# 243-436_USB-to-UART.net
KiCad netlist of a schematic drawn in Altium Designer
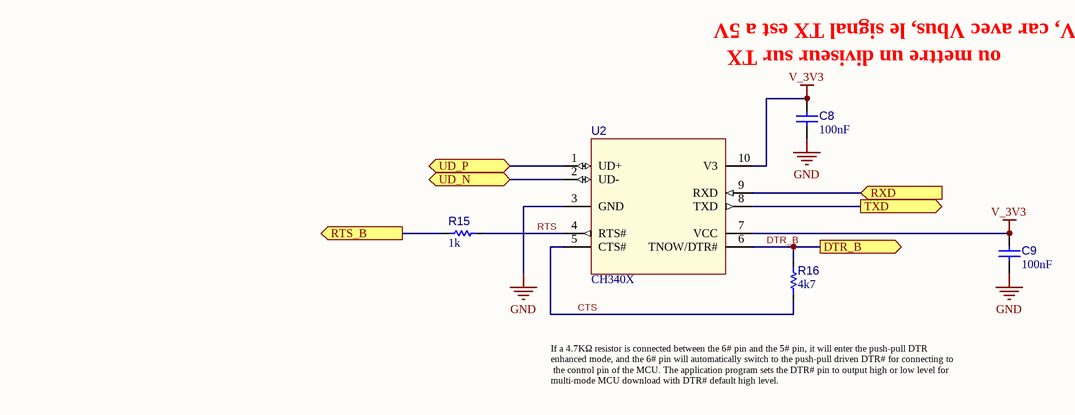
[diagram p0: 243-436_USB-to-UART.SchDoc]

(export (version "E")
  (design (tool "Eeschema 10.0.6"))
  (components
    (comp (ref "C8")
      (value "100nF")
      (footprint "C_1005[0402]")
      (description "Capacitor type 1")
      (fields (field (name "TOLERANCE") "10%") (field (name "Comment") "CAP CER 100nF 50V 0402"))
      (libsource (lib "TEP_243-Altium_DBLib") (part "capacitor"))
    )
    (comp (ref "C9")
      (value "100nF")
      (footprint "C_1005[0402]")
      (description "Capacitor type 1")
      (fields (field (name "TOLERANCE") "10%") (field (name "Comment") "CAP CER 100nF 50V 0402"))
      (libsource (lib "TEP_243-Altium_DBLib") (part "capacitor"))
    )
    (comp (ref "R15")
      (value "1k")
      (footprint "R_1005[0402]")
      (description "Resistor type 1")
      (fields (field (name "TOLERANCE") "1%") (field (name "Comment") "Res 1k 1% 0402"))
      (libsource (lib "TEP_243-Altium_DBLib") (part "resistor"))
    )
    (comp (ref "R16")
      (value "4k7")
      (footprint "R_1005[0402]")
      (description "Resistor type 1")
      (fields (field (name "TOLERANCE") "1%") (field (name "Comment") "Res 4k7 1% 0402"))
      (libsource (lib "TEP_243-Altium_DBLib") (part "resistor"))
    )
    (comp (ref "U2")
      (value "CH340X")
      (footprint "U_MSOP50P300X500-10(RM-10)_WO-TP")
      (description "IC USB to Serial Port")
      (libsource (lib "243-336_MP_Manette") (part "U_CH340X"))
    )
  )
  (nets
    (net (code "1") (name "/CTS") (class "Default")
      (node (ref "R16") (pin "1") (pinfunction "1_1") (pintype "passive"))
      (node (ref "U2") (pin "5") (pinfunction "CTS#_5") (pintype "passive"))
    )
    (net (code "2") (name "/DTR_B") (class "Default")
      (node (ref "R16") (pin "2") (pinfunction "2_2") (pintype "passive"))
      (node (ref "U2") (pin "6") (pinfunction "TNOW/DTR#_6") (pintype "passive"))
    )
    (net (code "3") (name "/RTS") (class "Default")
      (node (ref "R15") (pin "2") (pinfunction "2_2") (pintype "passive"))
      (node (ref "U2") (pin "4") (pinfunction "RTS#_4") (pintype "output"))
    )
    (net (code "4") (name "/RTS_B") (class "Default")
      (node (ref "R15") (pin "1") (pinfunction "1_1") (pintype "passive"))
    )
    (net (code "5") (name "/RXD") (class "Default")
      (node (ref "U2") (pin "9") (pinfunction "RXD_9") (pintype "input"))
    )
    (net (code "6") (name "/TXD") (class "Default")
      (node (ref "U2") (pin "8") (pinfunction "TXD_8") (pintype "output"))
    )
    (net (code "7") (name "/UD_N") (class "Default")
      (node (ref "U2") (pin "2") (pinfunction "UD-_2") (pintype "bidirectional"))
    )
    (net (code "8") (name "/UD_P") (class "Default")
      (node (ref "U2") (pin "1") (pinfunction "UD+_1") (pintype "bidirectional"))
    )
    (net (code "9") (name "GND") (class "Default")
      (node (ref "C8") (pin "1") (pinfunction "1_1") (pintype "passive"))
      (node (ref "C9") (pin "1") (pinfunction "1_1") (pintype "passive"))
      (node (ref "U2") (pin "3") (pinfunction "GND_3") (pintype "power_in"))
    )
    (net (code "10") (name "V_3V3") (class "Default")
      (node (ref "C8") (pin "2") (pinfunction "2_2") (pintype "passive"))
      (node (ref "C9") (pin "2") (pinfunction "2_2") (pintype "passive"))
      (node (ref "U2") (pin "10") (pinfunction "V3_10") (pintype "power_in"))
      (node (ref "U2") (pin "7") (pinfunction "VCC_7") (pintype "power_in"))
    )
  )
)
